# BT_interface.net
KiCad netlist of a schematic drawn in EAGLE
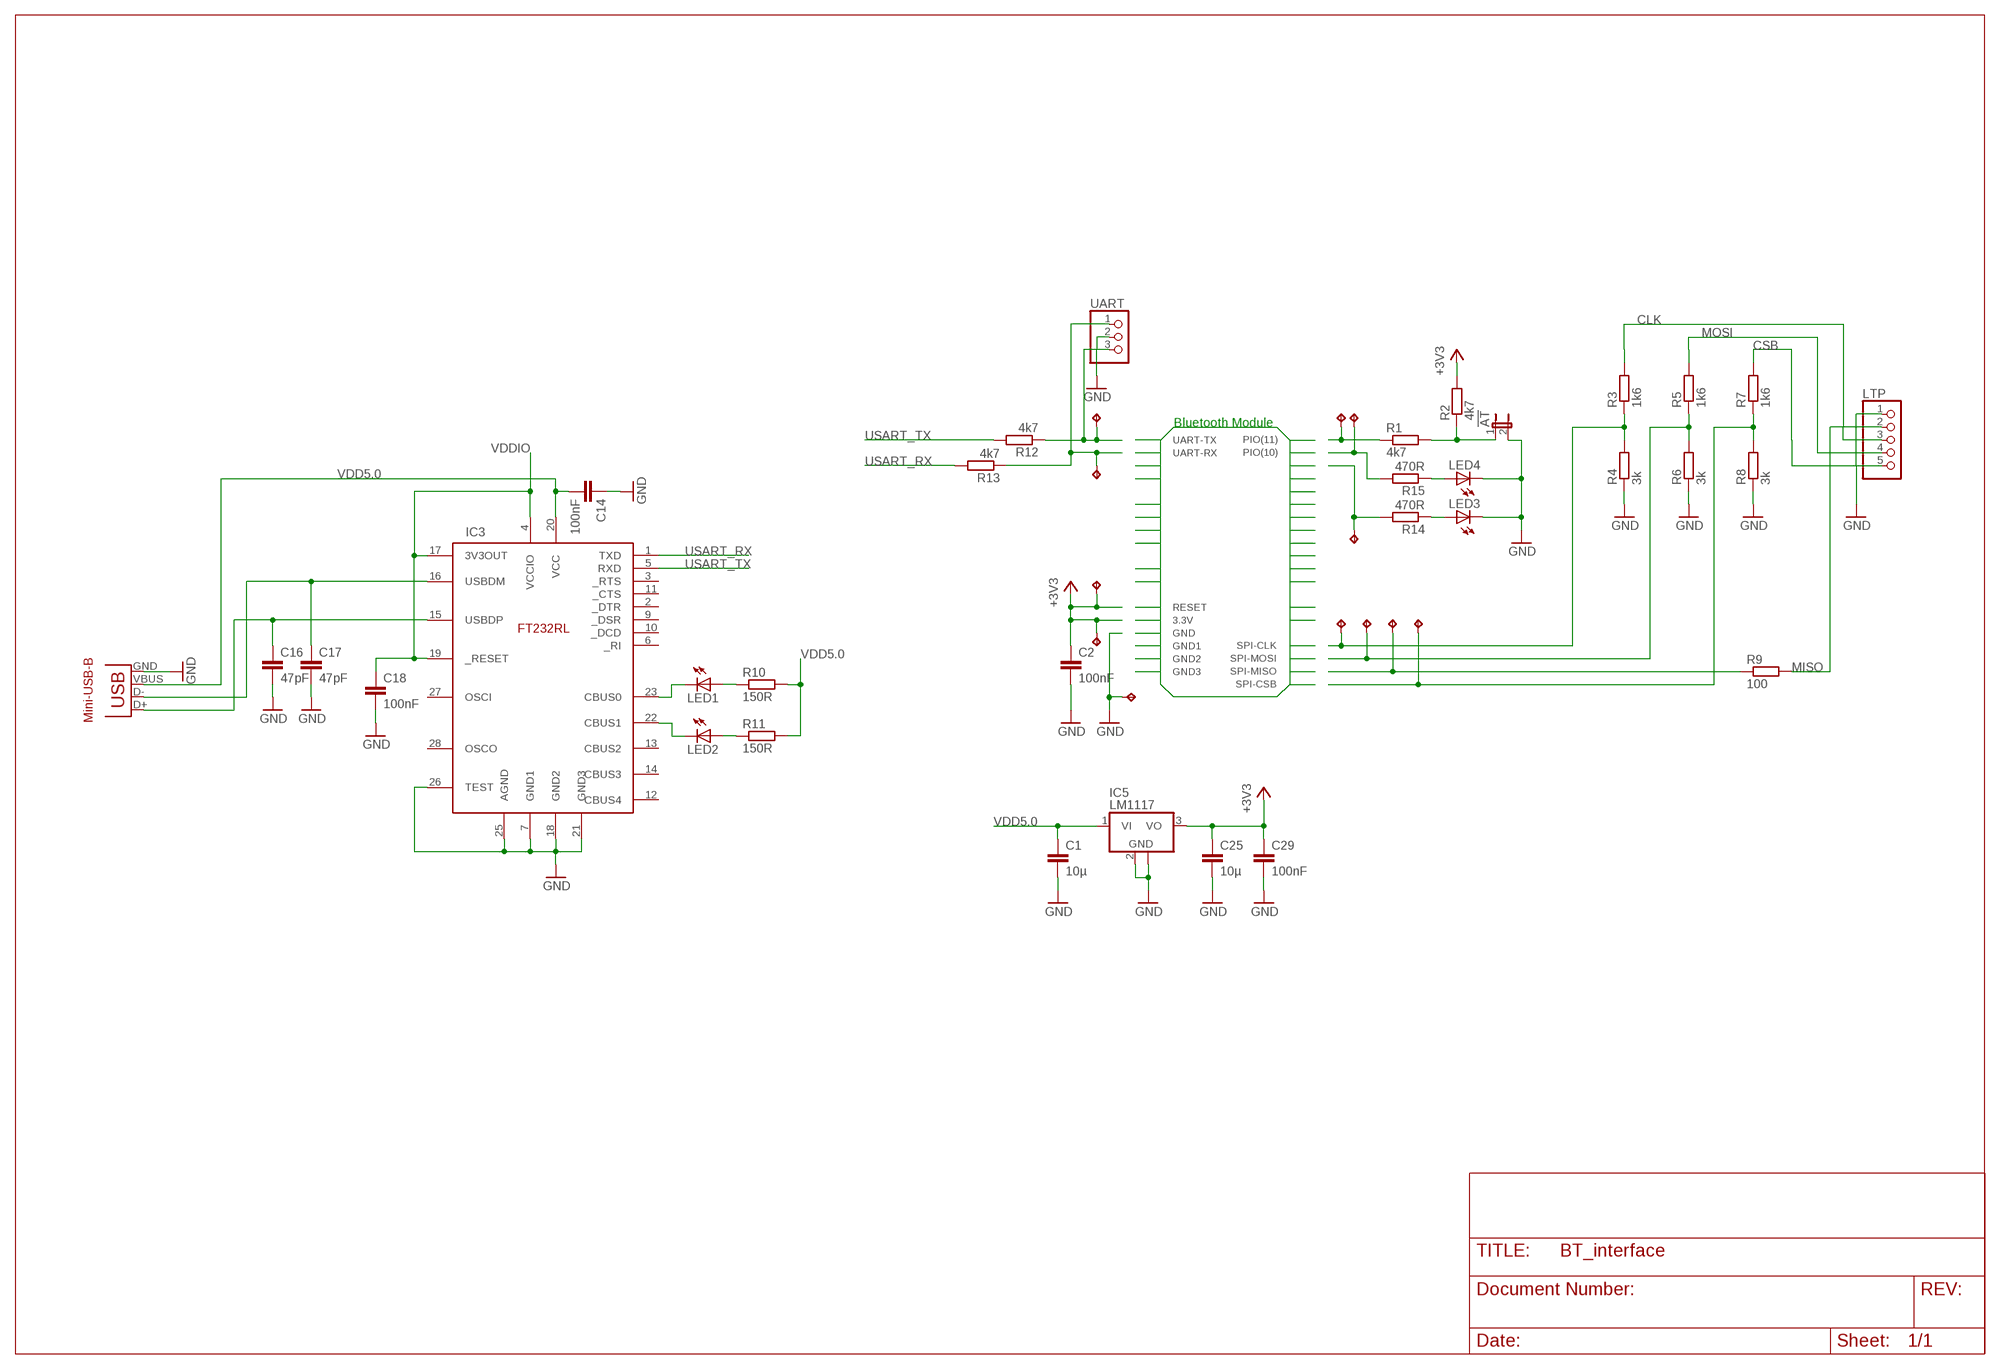
[diagram p0: schematic, sheet 1]

(export (version "E")
  (design (tool "Eeschema 10.0.6"))
  (components
    (comp (ref "!AT")
      (value "JUMPER-2PTH")
      (footprint "eagle-import:1X02")
      (libsource (lib "eagle-import") (part "JUMPER-2PTH"))
    )
    (comp (ref "C1")
      (value "10µ")
      (footprint "eagle-import:C0805")
      (libsource (lib "eagle-import") (part "C-EUC0805"))
    )
    (comp (ref "C2")
      (value "100nF")
      (footprint "eagle-import:C0805")
      (libsource (lib "eagle-import") (part "C-EUC0805"))
    )
    (comp (ref "C14")
      (value "100nF")
      (footprint "eagle-import:C0805")
      (libsource (lib "eagle-import") (part "C-EUC0805"))
    )
    (comp (ref "C16")
      (value "47pF")
      (footprint "eagle-import:C0805")
      (libsource (lib "eagle-import") (part "C-EUC0805"))
    )
    (comp (ref "C17")
      (value "47pF")
      (footprint "eagle-import:C0805")
      (libsource (lib "eagle-import") (part "C-EUC0805"))
    )
    (comp (ref "C18")
      (value "100nF")
      (footprint "eagle-import:C0805")
      (libsource (lib "eagle-import") (part "C-EUC0805"))
    )
    (comp (ref "C25")
      (value "10µ")
      (footprint "eagle-import:C0805")
      (libsource (lib "eagle-import") (part "C-EUC0805"))
    )
    (comp (ref "C29")
      (value "100nF")
      (footprint "eagle-import:C0805")
      (libsource (lib "eagle-import") (part "C-EUC0805"))
    )
    (comp (ref "IC3")
      (value "FT232RL")
      (footprint "eagle-import:SSOP28DB")
      (libsource (lib "eagle-import") (part "FT232RL"))
    )
    (comp (ref "IC5")
      (value "UA78M05DCY")
      (footprint "eagle-import:SOT223")
      (fields (field (name "LM1117") "LM1117"))
      (libsource (lib "eagle-import") (part "UA78MDCY05"))
    )
    (comp (ref "LED1")
      (value "LEDCHIPLED_0603")
      (footprint "eagle-import:CHIPLED_0603")
      (libsource (lib "eagle-import") (part "LEDCHIPLED_0603"))
    )
    (comp (ref "LED2")
      (value "LEDCHIPLED_0603")
      (footprint "eagle-import:CHIPLED_0603")
      (libsource (lib "eagle-import") (part "LEDCHIPLED_0603"))
    )
    (comp (ref "LED3")
      (value "LEDCHIPLED_0603")
      (footprint "eagle-import:CHIPLED_0603")
      (libsource (lib "eagle-import") (part "LEDCHIPLED_0603"))
    )
    (comp (ref "LED4")
      (value "LEDCHIPLED_0603")
      (footprint "eagle-import:CHIPLED_0603")
      (libsource (lib "eagle-import") (part "LEDCHIPLED_0603"))
    )
    (comp (ref "LTP")
      (value "PINHD-1X5")
      (footprint "eagle-import:1X05")
      (libsource (lib "eagle-import") (part "PINHD-1X5"))
    )
    (comp (ref "R1")
      (value "4k7")
      (footprint "eagle-import:R0805")
      (libsource (lib "eagle-import") (part "R-EU_R0805"))
    )
    (comp (ref "R2")
      (value "4k7")
      (footprint "eagle-import:R0805")
      (libsource (lib "eagle-import") (part "R-EU_R0805"))
    )
    (comp (ref "R3")
      (value "1k6")
      (footprint "eagle-import:R0805")
      (libsource (lib "eagle-import") (part "R-EU_R0805"))
    )
    (comp (ref "R4")
      (value "3k")
      (footprint "eagle-import:R0805")
      (libsource (lib "eagle-import") (part "R-EU_R0805"))
    )
    (comp (ref "R5")
      (value "1k6")
      (footprint "eagle-import:R0805")
      (libsource (lib "eagle-import") (part "R-EU_R0805"))
    )
    (comp (ref "R6")
      (value "3k")
      (footprint "eagle-import:R0805")
      (libsource (lib "eagle-import") (part "R-EU_R0805"))
    )
    (comp (ref "R7")
      (value "1k6")
      (footprint "eagle-import:R0805")
      (libsource (lib "eagle-import") (part "R-EU_R0805"))
    )
    (comp (ref "R8")
      (value "3k")
      (footprint "eagle-import:R0805")
      (libsource (lib "eagle-import") (part "R-EU_R0805"))
    )
    (comp (ref "R9")
      (value "100")
      (footprint "eagle-import:R0805")
      (libsource (lib "eagle-import") (part "R-EU_R0805"))
    )
    (comp (ref "R10")
      (value "150R")
      (footprint "eagle-import:R0805")
      (libsource (lib "eagle-import") (part "R-EU_R0805"))
    )
    (comp (ref "R11")
      (value "150R")
      (footprint "eagle-import:R0805")
      (libsource (lib "eagle-import") (part "R-EU_R0805"))
    )
    (comp (ref "R12")
      (value "4k7")
      (footprint "eagle-import:R0805")
      (libsource (lib "eagle-import") (part "R-EU_R0805"))
    )
    (comp (ref "R13")
      (value "4k7")
      (footprint "eagle-import:R0805")
      (libsource (lib "eagle-import") (part "R-EU_R0805"))
    )
    (comp (ref "R14")
      (value "470R")
      (footprint "eagle-import:R0805")
      (libsource (lib "eagle-import") (part "R-EU_R0805"))
    )
    (comp (ref "R15")
      (value "470R")
      (footprint "eagle-import:R0805")
      (libsource (lib "eagle-import") (part "R-EU_R0805"))
    )
    (comp (ref "U$2")
      (value "SPRING_HEADER")
      (footprint "eagle-import:SPRING_HEADER")
      (libsource (lib "eagle-import") (part "SPRING_HEADER"))
    )
    (comp (ref "U$3")
      (value "SPRING_HEADER")
      (footprint "eagle-import:SPRING_HEADER")
      (libsource (lib "eagle-import") (part "SPRING_HEADER"))
    )
    (comp (ref "U$4")
      (value "SPRING_HEADER")
      (footprint "eagle-import:SPRING_HEADER")
      (libsource (lib "eagle-import") (part "SPRING_HEADER"))
    )
    (comp (ref "U$5")
      (value "SPRING_HEADER")
      (footprint "eagle-import:SPRING_HEADER")
      (libsource (lib "eagle-import") (part "SPRING_HEADER"))
    )
    (comp (ref "U$6")
      (value "SPRING_HEADER")
      (footprint "eagle-import:SPRING_HEADER")
      (libsource (lib "eagle-import") (part "SPRING_HEADER"))
    )
    (comp (ref "U$7")
      (value "SPRING_HEADER")
      (footprint "eagle-import:SPRING_HEADER")
      (libsource (lib "eagle-import") (part "SPRING_HEADER"))
    )
    (comp (ref "U$8")
      (value "SPRING_HEADER")
      (footprint "eagle-import:SPRING_HEADER")
      (libsource (lib "eagle-import") (part "SPRING_HEADER"))
    )
    (comp (ref "U$9")
      (value "SPRING_HEADER")
      (footprint "eagle-import:SPRING_HEADER")
      (libsource (lib "eagle-import") (part "SPRING_HEADER"))
    )
    (comp (ref "U$10")
      (value "SPRING_HEADER")
      (footprint "eagle-import:SPRING_HEADER")
      (libsource (lib "eagle-import") (part "SPRING_HEADER"))
    )
    (comp (ref "U$11")
      (value "SPRING_HEADER")
      (footprint "eagle-import:SPRING_HEADER")
      (libsource (lib "eagle-import") (part "SPRING_HEADER"))
    )
    (comp (ref "U$12")
      (value "SPRING_HEADER")
      (footprint "eagle-import:SPRING_HEADER")
      (libsource (lib "eagle-import") (part "SPRING_HEADER"))
    )
    (comp (ref "U$13")
      (value "SPRING_HEADER")
      (footprint "eagle-import:SPRING_HEADER")
      (libsource (lib "eagle-import") (part "SPRING_HEADER"))
    )
    (comp (ref "UART")
      (value "PINHD-1X3")
      (footprint "eagle-import:1X03")
      (libsource (lib "eagle-import") (part "PINHD-1X3"))
    )
    (comp (ref "USB1")
      (value "USB-MB-S2")
      (footprint "eagle-import:USB-MP-S2")
      (libsource (lib "eagle-import") (part "USB-MB-S2"))
    )
  )
  (nets
    (net (code "1") (name "+3V3") (class "Default")
      (node (ref "C2") (pin "1") (pinfunction "1_1") (pintype "passive"))
      (node (ref "C25") (pin "1") (pinfunction "1_1") (pintype "passive"))
      (node (ref "C29") (pin "1") (pinfunction "1_1") (pintype "passive"))
      (node (ref "IC5") (pin "3") (pinfunction "VO_3") (pintype "passive"))
      (node (ref "R2") (pin "2") (pinfunction "2_2") (pintype "passive"))
      (node (ref "U$4") (pin "P$1") (pinfunction "TP_P$1") (pintype "input"))
      (node (ref "U$5") (pin "P$1") (pinfunction "TP_P$1") (pintype "input"))
    )
    (net (code "2") (name "/CLK") (class "Default")
      (node (ref "LTP") (pin "3") (pinfunction "3_3") (pintype "passive"))
      (node (ref "R3") (pin "2") (pinfunction "2_2") (pintype "passive"))
    )
    (net (code "3") (name "/CSB") (class "Default")
      (node (ref "LTP") (pin "5") (pinfunction "5_5") (pintype "passive"))
      (node (ref "R7") (pin "2") (pinfunction "2_2") (pintype "passive"))
    )
    (net (code "4") (name "/MISO") (class "Default")
      (node (ref "LTP") (pin "2") (pinfunction "2_2") (pintype "passive"))
      (node (ref "R9") (pin "2") (pinfunction "2_2") (pintype "passive"))
    )
    (net (code "5") (name "/MOSI") (class "Default")
      (node (ref "LTP") (pin "4") (pinfunction "4_4") (pintype "passive"))
      (node (ref "R5") (pin "2") (pinfunction "2_2") (pintype "passive"))
    )
    (net (code "6") (name "/USART_RX") (class "Default")
      (node (ref "IC3") (pin "1") (pinfunction "TXD_1") (pintype "output"))
      (node (ref "R13") (pin "2") (pinfunction "2_2") (pintype "passive"))
    )
    (net (code "7") (name "/USART_TX") (class "Default")
      (node (ref "IC3") (pin "5") (pinfunction "RXD_5") (pintype "input"))
      (node (ref "R12") (pin "2") (pinfunction "2_2") (pintype "passive"))
    )
    (net (code "8") (name "/VDD5.0") (class "Default")
      (node (ref "C1") (pin "1") (pinfunction "1_1") (pintype "passive"))
      (node (ref "C14") (pin "2") (pinfunction "2_2") (pintype "passive"))
      (node (ref "IC3") (pin "20") (pinfunction "VCC_20") (pintype "power_in"))
      (node (ref "IC5") (pin "1") (pinfunction "VI_1") (pintype "input"))
      (node (ref "R10") (pin "2") (pinfunction "2_2") (pintype "passive"))
      (node (ref "R11") (pin "2") (pinfunction "2_2") (pintype "passive"))
      (node (ref "USB1") (pin "VBUS") (pinfunction "VBUS_VBUS") (pintype "bidirectional"))
    )
    (net (code "9") (name "/VDDIO") (class "Default")
      (node (ref "C18") (pin "1") (pinfunction "1_1") (pintype "passive"))
      (node (ref "IC3") (pin "17") (pinfunction "3V3OUT_17") (pintype "output"))
      (node (ref "IC3") (pin "19") (pinfunction "_RESET_19") (pintype "input"))
      (node (ref "IC3") (pin "4") (pinfunction "VCCIO_4") (pintype "power_in"))
    )
    (net (code "10") (name "GND") (class "Default")
      (node (ref "!AT") (pin "2") (pinfunction "2_2") (pintype "passive"))
      (node (ref "C1") (pin "2") (pinfunction "2_2") (pintype "passive"))
      (node (ref "C14") (pin "1") (pinfunction "1_1") (pintype "passive"))
      (node (ref "C16") (pin "2") (pinfunction "2_2") (pintype "passive"))
      (node (ref "C17") (pin "2") (pinfunction "2_2") (pintype "passive"))
      (node (ref "C18") (pin "2") (pinfunction "2_2") (pintype "passive"))
      (node (ref "C2") (pin "2") (pinfunction "2_2") (pintype "passive"))
      (node (ref "C25") (pin "2") (pinfunction "2_2") (pintype "passive"))
      (node (ref "C29") (pin "2") (pinfunction "2_2") (pintype "passive"))
      (node (ref "IC3") (pin "18") (pinfunction "GND2_18") (pintype "power_in"))
      (node (ref "IC3") (pin "21") (pinfunction "GND3_21") (pintype "power_in"))
      (node (ref "IC3") (pin "25") (pinfunction "AGND_25") (pintype "power_in"))
      (node (ref "IC3") (pin "26") (pinfunction "TEST_26") (pintype "input"))
      (node (ref "IC3") (pin "7") (pinfunction "GND1_7") (pintype "power_in"))
      (node (ref "IC5") (pin "2") (pinfunction "GND_2") (pintype "passive"))
      (node (ref "IC5") (pin "4") (pinfunction "GND_4") (pintype "passive"))
      (node (ref "LED3") (pin "C") (pinfunction "C_C") (pintype "passive"))
      (node (ref "LED4") (pin "C") (pinfunction "C_C") (pintype "passive"))
      (node (ref "LTP") (pin "1") (pinfunction "1_1") (pintype "passive"))
      (node (ref "R4") (pin "1") (pinfunction "1_1") (pintype "passive"))
      (node (ref "R6") (pin "1") (pinfunction "1_1") (pintype "passive"))
      (node (ref "R8") (pin "1") (pinfunction "1_1") (pintype "passive"))
      (node (ref "U$6") (pin "P$1") (pinfunction "TP_P$1") (pintype "input"))
      (node (ref "UART") (pin "2") (pinfunction "2_2") (pintype "passive"))
      (node (ref "USB1") (pin "GND") (pinfunction "GND_GND") (pintype "bidirectional"))
    )
    (net (code "11") (name "Net-(!AT-Pad1)") (class "Default")
      (node (ref "!AT") (pin "1") (pinfunction "1_1") (pintype "passive"))
      (node (ref "R1") (pin "2") (pinfunction "2_2") (pintype "passive"))
      (node (ref "R2") (pin "1") (pinfunction "1_1") (pintype "passive"))
    )
    (net (code "12") (name "Net-(IC3-CBUS0)") (class "Default")
      (node (ref "IC3") (pin "23") (pinfunction "CBUS0_23") (pintype "bidirectional"))
      (node (ref "LED1") (pin "C") (pinfunction "C_C") (pintype "passive"))
    )
    (net (code "13") (name "Net-(IC3-CBUS1)") (class "Default")
      (node (ref "IC3") (pin "22") (pinfunction "CBUS1_22") (pintype "bidirectional"))
      (node (ref "LED2") (pin "C") (pinfunction "C_C") (pintype "passive"))
    )
    (net (code "14") (name "Net-(IC3-USBDM)") (class "Default")
      (node (ref "C17") (pin "1") (pinfunction "1_1") (pintype "passive"))
      (node (ref "IC3") (pin "16") (pinfunction "USBDM_16") (pintype "bidirectional"))
      (node (ref "USB1") (pin "D-") (pinfunction "D-_D-") (pintype "bidirectional"))
    )
    (net (code "15") (name "Net-(IC3-USBDP)") (class "Default")
      (node (ref "C16") (pin "1") (pinfunction "1_1") (pintype "passive"))
      (node (ref "IC3") (pin "15") (pinfunction "USBDP_15") (pintype "bidirectional"))
      (node (ref "USB1") (pin "D+") (pinfunction "D+_D+") (pintype "bidirectional"))
    )
    (net (code "16") (name "Net-(LED1-PadA)") (class "Default")
      (node (ref "LED1") (pin "A") (pinfunction "A_A") (pintype "passive"))
      (node (ref "R10") (pin "1") (pinfunction "1_1") (pintype "passive"))
    )
    (net (code "17") (name "Net-(LED2-PadA)") (class "Default")
      (node (ref "LED2") (pin "A") (pinfunction "A_A") (pintype "passive"))
      (node (ref "R11") (pin "1") (pinfunction "1_1") (pintype "passive"))
    )
    (net (code "18") (name "Net-(LED3-PadA)") (class "Default")
      (node (ref "LED3") (pin "A") (pinfunction "A_A") (pintype "passive"))
      (node (ref "R14") (pin "1") (pinfunction "1_1") (pintype "passive"))
    )
    (net (code "19") (name "Net-(LED4-PadA)") (class "Default")
      (node (ref "LED4") (pin "A") (pinfunction "A_A") (pintype "passive"))
      (node (ref "R15") (pin "1") (pinfunction "1_1") (pintype "passive"))
    )
    (net (code "20") (name "Net-(U$2-TP)") (class "Default")
      (node (ref "R12") (pin "1") (pinfunction "1_1") (pintype "passive"))
      (node (ref "U$2") (pin "P$1") (pinfunction "TP_P$1") (pintype "input"))
      (node (ref "UART") (pin "3") (pinfunction "3_3") (pintype "passive"))
    )
    (net (code "21") (name "Net-(U$3-TP)") (class "Default")
      (node (ref "R13") (pin "1") (pinfunction "1_1") (pintype "passive"))
      (node (ref "U$3") (pin "P$1") (pinfunction "TP_P$1") (pintype "input"))
      (node (ref "UART") (pin "1") (pinfunction "1_1") (pintype "passive"))
    )
    (net (code "22") (name "Net-(U$7-TP)") (class "Default")
      (node (ref "R5") (pin "1") (pinfunction "1_1") (pintype "passive"))
      (node (ref "R6") (pin "2") (pinfunction "2_2") (pintype "passive"))
      (node (ref "U$7") (pin "P$1") (pinfunction "TP_P$1") (pintype "input"))
    )
    (net (code "23") (name "Net-(U$8-TP)") (class "Default")
      (node (ref "R3") (pin "1") (pinfunction "1_1") (pintype "passive"))
      (node (ref "R4") (pin "2") (pinfunction "2_2") (pintype "passive"))
      (node (ref "U$8") (pin "P$1") (pinfunction "TP_P$1") (pintype "input"))
    )
    (net (code "24") (name "Net-(U$9-TP)") (class "Default")
      (node (ref "R1") (pin "1") (pinfunction "1_1") (pintype "passive"))
      (node (ref "U$9") (pin "P$1") (pinfunction "TP_P$1") (pintype "input"))
    )
    (net (code "25") (name "Net-(U$10-TP)") (class "Default")
      (node (ref "R9") (pin "1") (pinfunction "1_1") (pintype "passive"))
      (node (ref "U$10") (pin "P$1") (pinfunction "TP_P$1") (pintype "input"))
    )
    (net (code "26") (name "Net-(U$11-TP)") (class "Default")
      (node (ref "R7") (pin "1") (pinfunction "1_1") (pintype "passive"))
      (node (ref "R8") (pin "2") (pinfunction "2_2") (pintype "passive"))
      (node (ref "U$11") (pin "P$1") (pinfunction "TP_P$1") (pintype "input"))
    )
    (net (code "27") (name "Net-(U$12-TP)") (class "Default")
      (node (ref "R15") (pin "2") (pinfunction "2_2") (pintype "passive"))
      (node (ref "U$12") (pin "P$1") (pinfunction "TP_P$1") (pintype "input"))
    )
    (net (code "28") (name "Net-(U$13-TP)") (class "Default")
      (node (ref "R14") (pin "2") (pinfunction "2_2") (pintype "passive"))
      (node (ref "U$13") (pin "P$1") (pinfunction "TP_P$1") (pintype "input"))
    )
    (net (code "29") (name "unconnected-(IC3-CBUS2-Pad13)") (class "Default")
      (node (ref "IC3") (pin "13") (pinfunction "CBUS2_13") (pintype "bidirectional"))
    )
    (net (code "30") (name "unconnected-(IC3-CBUS3-Pad14)") (class "Default")
      (node (ref "IC3") (pin "14") (pinfunction "CBUS3_14") (pintype "bidirectional"))
    )
    (net (code "31") (name "unconnected-(IC3-CBUS4-Pad12)") (class "Default")
      (node (ref "IC3") (pin "12") (pinfunction "CBUS4_12") (pintype "bidirectional"))
    )
    (net (code "32") (name "unconnected-(IC3-OSCI-Pad27)") (class "Default")
      (node (ref "IC3") (pin "27") (pinfunction "OSCI_27") (pintype "input"))
    )
    (net (code "33") (name "unconnected-(IC3-OSCO-Pad28)") (class "Default")
      (node (ref "IC3") (pin "28") (pinfunction "OSCO_28") (pintype "output"))
    )
    (net (code "34") (name "unconnected-(IC3-_CTS-Pad11)") (class "Default")
      (node (ref "IC3") (pin "11") (pinfunction "_CTS_11") (pintype "input"))
    )
    (net (code "35") (name "unconnected-(IC3-_DCD-Pad10)") (class "Default")
      (node (ref "IC3") (pin "10") (pinfunction "_DCD_10") (pintype "input"))
    )
    (net (code "36") (name "unconnected-(IC3-_DSR-Pad9)") (class "Default")
      (node (ref "IC3") (pin "9") (pinfunction "_DSR_9") (pintype "input"))
    )
    (net (code "37") (name "unconnected-(IC3-_DTR-Pad2)") (class "Default")
      (node (ref "IC3") (pin "2") (pinfunction "_DTR_2") (pintype "output"))
    )
    (net (code "38") (name "unconnected-(IC3-_RI-Pad6)") (class "Default")
      (node (ref "IC3") (pin "6") (pinfunction "_RI_6") (pintype "input"))
    )
    (net (code "39") (name "unconnected-(IC3-_RTS-Pad3)") (class "Default")
      (node (ref "IC3") (pin "3") (pinfunction "_RTS_3") (pintype "output"))
    )
  )
)
